# PSX_DC_HID.net
KiCad netlist of a schematic drawn in EAGLE
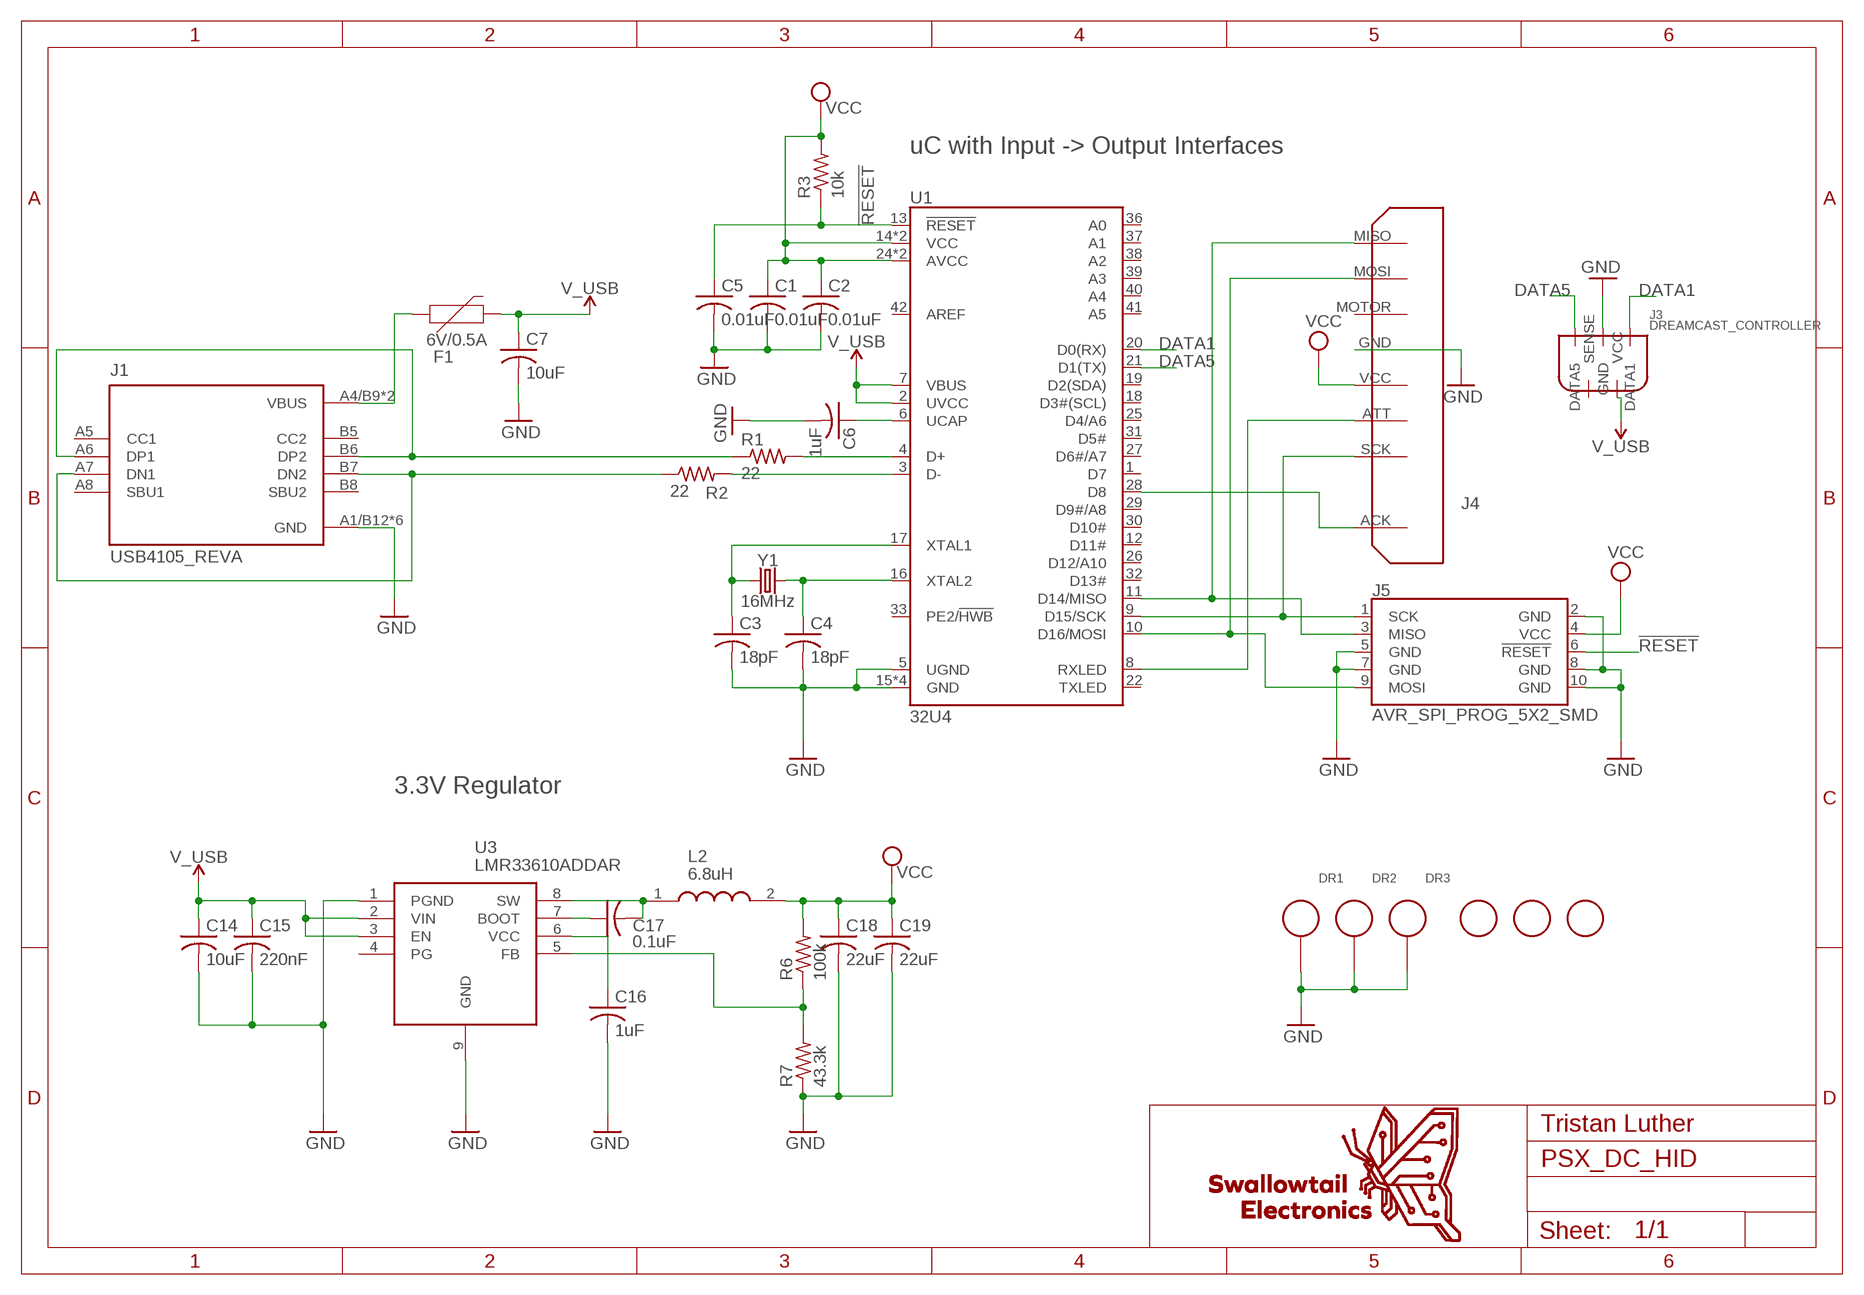
[diagram p0: schematic, sheet 1]

(export (version "E")
  (design (tool "Eeschema 10.0.6"))
  (components
    (comp (ref "C1")
      (value "0.01uF")
      (footprint "eagle-import:C0805")
      (libsource (lib "eagle-import") (part "C-USC0805"))
    )
    (comp (ref "C2")
      (value "0.01uF")
      (footprint "eagle-import:C0805")
      (libsource (lib "eagle-import") (part "C-USC0805"))
    )
    (comp (ref "C3")
      (value "18pF")
      (footprint "eagle-import:C0805")
      (libsource (lib "eagle-import") (part "C-USC0805"))
    )
    (comp (ref "C4")
      (value "18pF")
      (footprint "eagle-import:C0805")
      (libsource (lib "eagle-import") (part "C-USC0805"))
    )
    (comp (ref "C5")
      (value "0.01uF")
      (footprint "eagle-import:C0805")
      (libsource (lib "eagle-import") (part "C-USC0805"))
    )
    (comp (ref "C6")
      (value "1uF")
      (footprint "eagle-import:C0805")
      (libsource (lib "eagle-import") (part "C-USC0805"))
    )
    (comp (ref "C7")
      (value "10uF")
      (footprint "eagle-import:C0805")
      (libsource (lib "eagle-import") (part "C-USC0805"))
    )
    (comp (ref "C14")
      (value "10uF")
      (footprint "eagle-import:C0805")
      (libsource (lib "eagle-import") (part "Swallowtail_Passives_29140481_C-USC0805"))
    )
    (comp (ref "C15")
      (value "220nF")
      (footprint "eagle-import:C0805")
      (libsource (lib "eagle-import") (part "Swallowtail_Passives_29140481_C-USC0805"))
    )
    (comp (ref "C16")
      (value "1uF")
      (footprint "eagle-import:C0805")
      (libsource (lib "eagle-import") (part "Swallowtail_Passives_29140481_C-USC0805"))
    )
    (comp (ref "C17")
      (value "0.1uF")
      (footprint "eagle-import:C0805")
      (libsource (lib "eagle-import") (part "Swallowtail_Passives_29140481_C-USC0805"))
    )
    (comp (ref "C18")
      (value "22uF")
      (footprint "eagle-import:C0805")
      (libsource (lib "eagle-import") (part "Swallowtail_Passives_29140481_C-USC0805"))
    )
    (comp (ref "C19")
      (value "22uF")
      (footprint "eagle-import:C0805")
      (libsource (lib "eagle-import") (part "Swallowtail_Passives_29140481_C-USC0805"))
    )
    (comp (ref "DR1")
      (value "3MM_DRILL_GND")
      (footprint "eagle-import:3MM_DRILL_GND")
      (libsource (lib "eagle-import") (part "3MM_DRILL_GND"))
    )
    (comp (ref "DR2")
      (value "3MM_DRILL_GND")
      (footprint "eagle-import:3MM_DRILL_GND")
      (libsource (lib "eagle-import") (part "3MM_DRILL_GND"))
    )
    (comp (ref "DR3")
      (value "3MM_DRILL_GND")
      (footprint "eagle-import:3MM_DRILL_GND")
      (libsource (lib "eagle-import") (part "3MM_DRILL_GND"))
    )
    (comp (ref "F1")
      (value "6V/0.5A")
      (footprint "eagle-import:1206")
      (libsource (lib "eagle-import") (part "PPTC_HALF-AMP"))
    )
    (comp (ref "J1")
      (value "USB4105_REVA")
      (footprint "eagle-import:GCT_USB4105_REVA")
      (fields
        (field (name "DIGI-KEY_PART_NUMBER") "2073-USB4105-GF-ACT-ND")
        (field (name "MF") "Global Connector Technology")
        (field (name "MP") "USB4105")
      )
      (libsource (lib "eagle-import") (part "USB4105_REVA"))
    )
    (comp (ref "J3")
      (value "DREAMCAST_CONTROLLER")
      (footprint "eagle-import:1_05X2MM")
      (libsource (lib "eagle-import") (part "DREAMCAST_CONTROLLER"))
    )
    (comp (ref "J4")
      (value "PSX_CONTROLLERPSX_HORIZONTAL")
      (footprint "eagle-import:PSX_HORIZONTAL")
      (libsource (lib "eagle-import") (part "PSX_CONTROLLERPSX_HORIZONTAL"))
    )
    (comp (ref "J5")
      (value "AVR_SPI_PROG_5X2_SMD")
      (footprint "eagle-import:SAMTECH_FTSH-105-01")
      (libsource (lib "eagle-import") (part "AVR_SPI_PROG_5X2_SMD"))
    )
    (comp (ref "L2")
      (value "6.8uH")
      (footprint "eagle-import:INDPM5752X150N")
      (fields
        (field (name "ARROW_PART_NUMBER") "SRP5015TA-2R2M")
        (field (name "MOUSER_PART_NUMBER") "652-SRP5015TA-2R2M")
      )
      (libsource (lib "eagle-import") (part "SRP5015TA-2R2M"))
    )
    (comp (ref "R1")
      (value "22")
      (footprint "eagle-import:R0805")
      (libsource (lib "eagle-import") (part "R-US_R0805"))
    )
    (comp (ref "R2")
      (value "22")
      (footprint "eagle-import:R0805")
      (libsource (lib "eagle-import") (part "R-US_R0805"))
    )
    (comp (ref "R3")
      (value "10k")
      (footprint "eagle-import:R0805")
      (libsource (lib "eagle-import") (part "R-US_R0805"))
    )
    (comp (ref "R6")
      (value "100k")
      (footprint "eagle-import:R0805")
      (libsource (lib "eagle-import") (part "Swallowtail_Passives_29140481_R-US_R0805"))
    )
    (comp (ref "R7")
      (value "43.3k")
      (footprint "eagle-import:R0805")
      (libsource (lib "eagle-import") (part "Swallowtail_Passives_29140481_R-US_R0805"))
    )
    (comp (ref "U$2")
      (value "FIDUCIAL")
      (footprint "eagle-import:FIDUCIAL_1MM")
      (libsource (lib "eagle-import") (part "FIDUCIAL"))
    )
    (comp (ref "U$3")
      (value "FIDUCIAL")
      (footprint "eagle-import:FIDUCIAL_1MM")
      (libsource (lib "eagle-import") (part "FIDUCIAL"))
    )
    (comp (ref "U$4")
      (value "FIDUCIAL")
      (footprint "eagle-import:FIDUCIAL_1MM")
      (libsource (lib "eagle-import") (part "FIDUCIAL"))
    )
    (comp (ref "U1")
      (value "32U4")
      (footprint "eagle-import:TQFP44")
      (libsource (lib "eagle-import") (part "ATMEGA32U4-ARDUINOTQFP-44"))
    )
    (comp (ref "U3")
      (value "LMR33610ADDAR")
      (footprint "eagle-import:SOIC127P600X170-9N")
      (fields
        (field (name "ARROW_PART_NUMBER") "LMR33630ADDAR")
        (field (name "MOUSER_PART_NUMBER") "595-LMR33630ADDAR")
      )
      (libsource (lib "eagle-import") (part "LMR33610ADDAR"))
    )
    (comp (ref "Y1")
      (value "16MHz")
      (footprint "eagle-import:CRYSTAL-SMD-5X3.2-4PAD")
      (libsource (lib "eagle-import") (part "CRYSTAL-16MHZSMD-5X3.2"))
    )
  )
  (nets
    (net (code "1") (name "/DATA1") (class "Default")
      (node (ref "J3") (pin "1") (pinfunction "DATA1_1") (pintype "bidirectional"))
      (node (ref "U1") (pin "20") (pinfunction "D0(RX)_20") (pintype "bidirectional"))
    )
    (net (code "2") (name "/DATA5") (class "Default")
      (node (ref "J3") (pin "2") (pinfunction "DATA5_2") (pintype "bidirectional"))
      (node (ref "U1") (pin "21") (pinfunction "D1(TX)_21") (pintype "bidirectional"))
    )
    (net (code "3") (name "/~{RESET}") (class "Default")
      (node (ref "C5") (pin "1") (pinfunction "1_1") (pintype "passive"))
      (node (ref "J5") (pin "6") (pinfunction "~{RESET}_6") (pintype "bidirectional"))
      (node (ref "R3") (pin "1") (pinfunction "1_1") (pintype "passive"))
      (node (ref "U1") (pin "13") (pinfunction "~{RESET}_13") (pintype "bidirectional"))
    )
    (net (code "4") (name "GND") (class "Default")
      (node (ref "C1") (pin "2") (pinfunction "2_2") (pintype "passive"))
      (node (ref "C14") (pin "2") (pinfunction "2_2") (pintype "passive"))
      (node (ref "C15") (pin "2") (pinfunction "2_2") (pintype "passive"))
      (node (ref "C16") (pin "2") (pinfunction "2_2") (pintype "passive"))
      (node (ref "C18") (pin "2") (pinfunction "2_2") (pintype "passive"))
      (node (ref "C19") (pin "2") (pinfunction "2_2") (pintype "passive"))
      (node (ref "C2") (pin "2") (pinfunction "2_2") (pintype "passive"))
      (node (ref "C3") (pin "2") (pinfunction "2_2") (pintype "passive"))
      (node (ref "C4") (pin "2") (pinfunction "2_2") (pintype "passive"))
      (node (ref "C5") (pin "2") (pinfunction "2_2") (pintype "passive"))
      (node (ref "C6") (pin "2") (pinfunction "2_2") (pintype "passive"))
      (node (ref "C7") (pin "2") (pinfunction "2_2") (pintype "passive"))
      (node (ref "DR1") (pin "DR") (pinfunction "D$1_DR") (pintype "bidirectional"))
      (node (ref "DR2") (pin "DR") (pinfunction "D$1_DR") (pintype "bidirectional"))
      (node (ref "DR3") (pin "DR") (pinfunction "D$1_DR") (pintype "bidirectional"))
      (node (ref "J1") (pin "A1/B12") (pinfunction "GND_A1/B12") (pintype "power_in"))
      (node (ref "J1") (pin "B1/A12") (pinfunction "GND_B1/A12") (pintype "power_in"))
      (node (ref "J1") (pin "G1") (pinfunction "GND_G1") (pintype "power_in"))
      (node (ref "J1") (pin "G2") (pinfunction "GND_G2") (pintype "power_in"))
      (node (ref "J1") (pin "G3") (pinfunction "GND_G3") (pintype "power_in"))
      (node (ref "J1") (pin "G4") (pinfunction "GND_G4") (pintype "power_in"))
      (node (ref "J3") (pin "3") (pinfunction "GND_3") (pintype "power_in"))
      (node (ref "J4") (pin "GND") (pinfunction "GND_GND") (pintype "bidirectional"))
      (node (ref "J5") (pin "10") (pinfunction "GND_10") (pintype "bidirectional"))
      (node (ref "J5") (pin "2") (pinfunction "GND_2") (pintype "bidirectional"))
      (node (ref "J5") (pin "5") (pinfunction "GND_5") (pintype "bidirectional"))
      (node (ref "J5") (pin "7") (pinfunction "GND_7") (pintype "bidirectional"))
      (node (ref "J5") (pin "8") (pinfunction "GND_8") (pintype "bidirectional"))
      (node (ref "R7") (pin "1") (pinfunction "1_1") (pintype "passive"))
      (node (ref "U1") (pin "15") (pinfunction "GND_15") (pintype "bidirectional"))
      (node (ref "U1") (pin "23") (pinfunction "GND_23") (pintype "bidirectional"))
      (node (ref "U1") (pin "35") (pinfunction "GND_35") (pintype "bidirectional"))
      (node (ref "U1") (pin "43") (pinfunction "GND_43") (pintype "bidirectional"))
      (node (ref "U1") (pin "5") (pinfunction "UGND_5") (pintype "bidirectional"))
      (node (ref "U3") (pin "1") (pinfunction "PGND_1") (pintype "bidirectional"))
      (node (ref "U3") (pin "9") (pinfunction "GND_9") (pintype "bidirectional"))
    )
    (net (code "5") (name "Net-(F1-Pad1)") (class "Default")
      (node (ref "F1") (pin "1") (pinfunction "1_1") (pintype "bidirectional"))
      (node (ref "J1") (pin "A4/B9") (pinfunction "VBUS_A4/B9") (pintype "power_in"))
      (node (ref "J1") (pin "B4/A9") (pinfunction "VBUS_B4/A9") (pintype "power_in"))
    )
    (net (code "6") (name "Net-(J1-DN1)") (class "Default")
      (node (ref "J1") (pin "A7") (pinfunction "DN1_A7") (pintype "bidirectional"))
      (node (ref "J1") (pin "B7") (pinfunction "DN2_B7") (pintype "bidirectional"))
      (node (ref "R2") (pin "1") (pinfunction "1_1") (pintype "passive"))
    )
    (net (code "7") (name "Net-(J1-DP1)") (class "Default")
      (node (ref "J1") (pin "A6") (pinfunction "DP1_A6") (pintype "bidirectional"))
      (node (ref "J1") (pin "B6") (pinfunction "DP2_B6") (pintype "bidirectional"))
      (node (ref "R1") (pin "1") (pinfunction "1_1") (pintype "passive"))
    )
    (net (code "8") (name "Net-(J5-MISO)") (class "Default")
      (node (ref "J4") (pin "MISO") (pinfunction "MISO_MISO") (pintype "bidirectional"))
      (node (ref "J5") (pin "3") (pinfunction "MISO_3") (pintype "bidirectional"))
      (node (ref "U1") (pin "11") (pinfunction "D14/MISO_11") (pintype "bidirectional"))
    )
    (net (code "9") (name "Net-(J5-MOSI)") (class "Default")
      (node (ref "J4") (pin "MOSI") (pinfunction "MOSI_MOSI") (pintype "bidirectional"))
      (node (ref "J5") (pin "9") (pinfunction "MOSI_9") (pintype "bidirectional"))
      (node (ref "U1") (pin "10") (pinfunction "D16/MOSI_10") (pintype "bidirectional"))
    )
    (net (code "10") (name "Net-(J5-SCK)") (class "Default")
      (node (ref "J4") (pin "SCK") (pinfunction "SCK_SCK") (pintype "bidirectional"))
      (node (ref "J5") (pin "1") (pinfunction "SCK_1") (pintype "bidirectional"))
      (node (ref "U1") (pin "9") (pinfunction "D15/SCK_9") (pintype "bidirectional"))
    )
    (net (code "11") (name "Net-(U1-D+)") (class "Default")
      (node (ref "R1") (pin "2") (pinfunction "2_2") (pintype "passive"))
      (node (ref "U1") (pin "4") (pinfunction "D+_4") (pintype "bidirectional"))
    )
    (net (code "12") (name "Net-(U1-D-)") (class "Default")
      (node (ref "R2") (pin "2") (pinfunction "2_2") (pintype "passive"))
      (node (ref "U1") (pin "3") (pinfunction "D-_3") (pintype "bidirectional"))
    )
    (net (code "13") (name "Net-(U1-D8)") (class "Default")
      (node (ref "J4") (pin "ACK") (pinfunction "ACK_ACK") (pintype "bidirectional"))
      (node (ref "U1") (pin "28") (pinfunction "D8_28") (pintype "bidirectional"))
    )
    (net (code "14") (name "Net-(U1-RXLED)") (class "Default")
      (node (ref "J4") (pin "ATT") (pinfunction "ATT_ATT") (pintype "bidirectional"))
      (node (ref "U1") (pin "8") (pinfunction "RXLED_8") (pintype "bidirectional"))
    )
    (net (code "15") (name "Net-(U1-UCAP)") (class "Default")
      (node (ref "C6") (pin "1") (pinfunction "1_1") (pintype "passive"))
      (node (ref "U1") (pin "6") (pinfunction "UCAP_6") (pintype "bidirectional"))
    )
    (net (code "16") (name "Net-(U1-XTAL1)") (class "Default")
      (node (ref "C3") (pin "1") (pinfunction "1_1") (pintype "passive"))
      (node (ref "U1") (pin "17") (pinfunction "XTAL1_17") (pintype "bidirectional"))
      (node (ref "Y1") (pin "1") (pinfunction "1_1") (pintype "passive"))
    )
    (net (code "17") (name "Net-(U1-XTAL2)") (class "Default")
      (node (ref "C4") (pin "1") (pinfunction "1_1") (pintype "passive"))
      (node (ref "U1") (pin "16") (pinfunction "XTAL2_16") (pintype "bidirectional"))
      (node (ref "Y1") (pin "3") (pinfunction "2_3") (pintype "passive"))
    )
    (net (code "18") (name "Net-(U3-BOOT)") (class "Default")
      (node (ref "C17") (pin "1") (pinfunction "1_1") (pintype "passive"))
      (node (ref "U3") (pin "7") (pinfunction "BOOT_7") (pintype "bidirectional"))
    )
    (net (code "19") (name "Net-(U3-FB)") (class "Default")
      (node (ref "R6") (pin "1") (pinfunction "1_1") (pintype "passive"))
      (node (ref "R7") (pin "2") (pinfunction "2_2") (pintype "passive"))
      (node (ref "U3") (pin "5") (pinfunction "FB_5") (pintype "bidirectional"))
    )
    (net (code "20") (name "Net-(U3-SW)") (class "Default")
      (node (ref "C17") (pin "2") (pinfunction "2_2") (pintype "passive"))
      (node (ref "L2") (pin "1") (pinfunction "1_1") (pintype "bidirectional"))
      (node (ref "U3") (pin "8") (pinfunction "SW_8") (pintype "bidirectional"))
    )
    (net (code "21") (name "Net-(U3-VCC)") (class "Default")
      (node (ref "C16") (pin "1") (pinfunction "1_1") (pintype "passive"))
      (node (ref "U3") (pin "6") (pinfunction "VCC_6") (pintype "bidirectional"))
    )
    (net (code "22") (name "VCC") (class "Default")
      (node (ref "C1") (pin "1") (pinfunction "1_1") (pintype "passive"))
      (node (ref "C18") (pin "1") (pinfunction "1_1") (pintype "passive"))
      (node (ref "C19") (pin "1") (pinfunction "1_1") (pintype "passive"))
      (node (ref "C2") (pin "1") (pinfunction "1_1") (pintype "passive"))
      (node (ref "J4") (pin "VCC") (pinfunction "VCC_VCC") (pintype "bidirectional"))
      (node (ref "J5") (pin "4") (pinfunction "VCC_4") (pintype "bidirectional"))
      (node (ref "L2") (pin "2") (pinfunction "2_2") (pintype "bidirectional"))
      (node (ref "R3") (pin "2") (pinfunction "2_2") (pintype "passive"))
      (node (ref "R6") (pin "2") (pinfunction "2_2") (pintype "passive"))
      (node (ref "U1") (pin "14") (pinfunction "VCC_14") (pintype "bidirectional"))
      (node (ref "U1") (pin "24") (pinfunction "AVCC_24") (pintype "bidirectional"))
      (node (ref "U1") (pin "34") (pinfunction "VCC_34") (pintype "bidirectional"))
      (node (ref "U1") (pin "44") (pinfunction "AVCC_44") (pintype "bidirectional"))
    )
    (net (code "23") (name "V_USB") (class "Default")
      (node (ref "C14") (pin "1") (pinfunction "1_1") (pintype "passive"))
      (node (ref "C15") (pin "1") (pinfunction "1_1") (pintype "passive"))
      (node (ref "C7") (pin "1") (pinfunction "1_1") (pintype "passive"))
      (node (ref "F1") (pin "2") (pinfunction "2_2") (pintype "bidirectional"))
      (node (ref "J3") (pin "5") (pinfunction "VCC_5") (pintype "power_in"))
      (node (ref "U1") (pin "2") (pinfunction "UVCC_2") (pintype "bidirectional"))
      (node (ref "U1") (pin "7") (pinfunction "VBUS_7") (pintype "bidirectional"))
      (node (ref "U3") (pin "2") (pinfunction "VIN_2") (pintype "bidirectional"))
      (node (ref "U3") (pin "3") (pinfunction "EN_3") (pintype "bidirectional"))
    )
    (net (code "24") (name "unconnected-(J1-CC1-PadA5)") (class "Default")
      (node (ref "J1") (pin "A5") (pinfunction "CC1_A5") (pintype "bidirectional"))
    )
    (net (code "25") (name "unconnected-(J1-CC2-PadB5)") (class "Default")
      (node (ref "J1") (pin "B5") (pinfunction "CC2_B5") (pintype "bidirectional"))
    )
    (net (code "26") (name "unconnected-(J1-SBU1-PadA8)") (class "Default")
      (node (ref "J1") (pin "A8") (pinfunction "SBU1_A8") (pintype "bidirectional"))
    )
    (net (code "27") (name "unconnected-(J1-SBU2-PadB8)") (class "Default")
      (node (ref "J1") (pin "B8") (pinfunction "SBU2_B8") (pintype "bidirectional"))
    )
    (net (code "28") (name "unconnected-(J3-SENSE-Pad4)") (class "Default")
      (node (ref "J3") (pin "4") (pinfunction "SENSE_4") (pintype "bidirectional"))
    )
    (net (code "29") (name "unconnected-(J4-PadMOTOR)") (class "Default")
      (node (ref "J4") (pin "MOTOR") (pinfunction "MOTOR_MOTOR") (pintype "bidirectional"))
    )
    (net (code "30") (name "unconnected-(U1-A0-Pad36)") (class "Default")
      (node (ref "U1") (pin "36") (pinfunction "A0_36") (pintype "bidirectional"))
    )
    (net (code "31") (name "unconnected-(U1-A1-Pad37)") (class "Default")
      (node (ref "U1") (pin "37") (pinfunction "A1_37") (pintype "bidirectional"))
    )
    (net (code "32") (name "unconnected-(U1-A2-Pad38)") (class "Default")
      (node (ref "U1") (pin "38") (pinfunction "A2_38") (pintype "bidirectional"))
    )
    (net (code "33") (name "unconnected-(U1-A3-Pad39)") (class "Default")
      (node (ref "U1") (pin "39") (pinfunction "A3_39") (pintype "bidirectional"))
    )
    (net (code "34") (name "unconnected-(U1-A4-Pad40)") (class "Default")
      (node (ref "U1") (pin "40") (pinfunction "A4_40") (pintype "bidirectional"))
    )
    (net (code "35") (name "unconnected-(U1-A5-Pad41)") (class "Default")
      (node (ref "U1") (pin "41") (pinfunction "A5_41") (pintype "bidirectional"))
    )
    (net (code "36") (name "unconnected-(U1-AREF-Pad42)") (class "Default")
      (node (ref "U1") (pin "42") (pinfunction "AREF_42") (pintype "bidirectional"))
    )
    (net (code "37") (name "unconnected-(U1-D2(SDA)-Pad19)") (class "Default")
      (node (ref "U1") (pin "19") (pinfunction "D2(SDA)_19") (pintype "bidirectional"))
    )
    (net (code "38") (name "unconnected-(U1-D3#(SCL)-Pad18)") (class "Default")
      (node (ref "U1") (pin "18") (pinfunction "D3#(SCL)_18") (pintype "bidirectional"))
    )
    (net (code "39") (name "unconnected-(U1-D4{slash}A6-Pad25)") (class "Default")
      (node (ref "U1") (pin "25") (pinfunction "D4/A6_25") (pintype "bidirectional"))
    )
    (net (code "40") (name "unconnected-(U1-D5#-Pad31)") (class "Default")
      (node (ref "U1") (pin "31") (pinfunction "D5#_31") (pintype "bidirectional"))
    )
    (net (code "41") (name "unconnected-(U1-D6#{slash}A7-Pad27)") (class "Default")
      (node (ref "U1") (pin "27") (pinfunction "D6#/A7_27") (pintype "bidirectional"))
    )
    (net (code "42") (name "unconnected-(U1-D7-Pad1)") (class "Default")
      (node (ref "U1") (pin "1") (pinfunction "D7_1") (pintype "bidirectional"))
    )
    (net (code "43") (name "unconnected-(U1-D9#{slash}A8-Pad29)") (class "Default")
      (node (ref "U1") (pin "29") (pinfunction "D9#/A8_29") (pintype "bidirectional"))
    )
    (net (code "44") (name "unconnected-(U1-D10#-Pad30)") (class "Default")
      (node (ref "U1") (pin "30") (pinfunction "D10#_30") (pintype "bidirectional"))
    )
    (net (code "45") (name "unconnected-(U1-D11#-Pad12)") (class "Default")
      (node (ref "U1") (pin "12") (pinfunction "D11#_12") (pintype "bidirectional"))
    )
    (net (code "46") (name "unconnected-(U1-D12{slash}A10-Pad26)") (class "Default")
      (node (ref "U1") (pin "26") (pinfunction "D12/A10_26") (pintype "bidirectional"))
    )
    (net (code "47") (name "unconnected-(U1-D13#-Pad32)") (class "Default")
      (node (ref "U1") (pin "32") (pinfunction "D13#_32") (pintype "bidirectional"))
    )
    (net (code "48") (name "unconnected-(U1-PE2{slash}~{HWB}-Pad33)") (class "Default")
      (node (ref "U1") (pin "33") (pinfunction "PE2/~{HWB}_33") (pintype "bidirectional"))
    )
    (net (code "49") (name "unconnected-(U1-TXLED-Pad22)") (class "Default")
      (node (ref "U1") (pin "22") (pinfunction "TXLED_22") (pintype "bidirectional"))
    )
    (net (code "50") (name "unconnected-(U3-PG-Pad4)") (class "Default")
      (node (ref "U3") (pin "4") (pinfunction "PG_4") (pintype "bidirectional"))
    )
  )
)
